# CPU2.net
KiCad netlist of a schematic drawn in Altium Designer
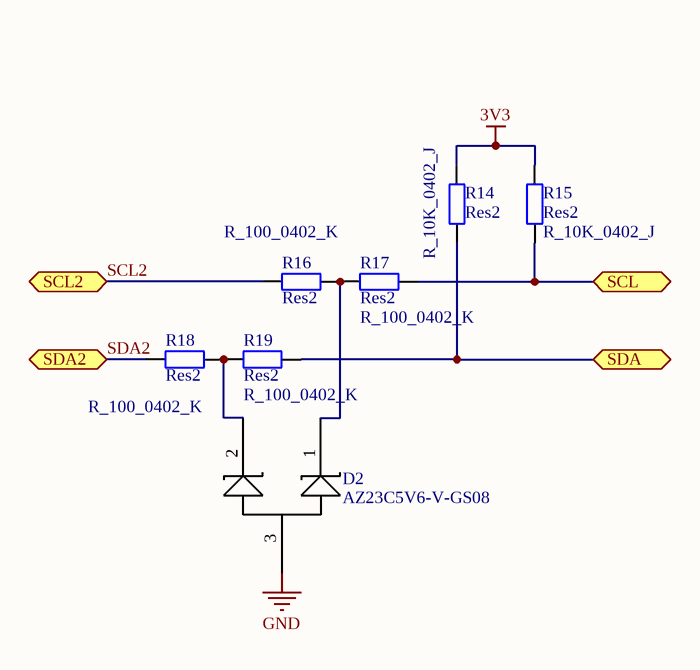
[diagram p0: CPU2.SchDoc]

(export (version "E")
  (design (tool "Eeschema 10.0.6"))
  (components
    (comp (ref "D2")
      (value "AZ23C5V6-V-GS08")
      (footprint "SOT-23_N")
      (description "Zener Diodes 5.6 Volt 0.3W 5% CA")
      (fields (field (name "MANUFACTURER") "Vishay Semiconductors"))
      (libsource (lib "BrewBit") (part "AZ23C5V6-V-GS08"))
    )
    (comp (ref "R14")
      (value "Res2")
      (footprint "R_0402")
      (description "Resistor")
      (fields (field (name "ALTIUM_VALUE") "R_10K_0402_J") (field (name "PUBLISHER") "Altium Limited"))
      (libsource (lib "") (part "Res2_1"))
    )
    (comp (ref "R15")
      (value "Res2")
      (footprint "R_0402")
      (description "Resistor")
      (fields (field (name "ALTIUM_VALUE") "R_10K_0402_J") (field (name "PUBLISHER") "Altium Limited"))
      (libsource (lib "") (part "Res2_1"))
    )
    (comp (ref "R16")
      (value "Res2")
      (footprint "R_0402")
      (description "Resistor")
      (fields (field (name "ALTIUM_VALUE") "R_100_0402_K") (field (name "PUBLISHER") "Altium Limited"))
      (libsource (lib "Miscellaneous Devices") (part "Res2"))
    )
    (comp (ref "R17")
      (value "Res2")
      (footprint "R_0402")
      (description "Resistor")
      (fields (field (name "ALTIUM_VALUE") "R_100_0402_K") (field (name "PUBLISHER") "Altium Limited"))
      (libsource (lib "Miscellaneous Devices") (part "Res2"))
    )
    (comp (ref "R18")
      (value "Res2")
      (footprint "R_0402")
      (description "Resistor")
      (fields (field (name "ALTIUM_VALUE") "R_100_0402_K") (field (name "PUBLISHER") "Altium Limited"))
      (libsource (lib "Miscellaneous Devices") (part "Res2"))
    )
    (comp (ref "R19")
      (value "Res2")
      (footprint "R_0402")
      (description "Resistor")
      (fields (field (name "ALTIUM_VALUE") "R_100_0402_K") (field (name "PUBLISHER") "Altium Limited"))
      (libsource (lib "Miscellaneous Devices") (part "Res2"))
    )
  )
  (nets
    (net (code "1") (name "/SCL") (class "Default")
      (node (ref "R15") (pin "1") (pinfunction "1_1") (pintype "passive"))
      (node (ref "R17") (pin "2") (pinfunction "2_2") (pintype "passive"))
    )
    (net (code "2") (name "/SCL2") (class "Default")
      (node (ref "R16") (pin "1") (pinfunction "1_1") (pintype "passive"))
    )
    (net (code "3") (name "/SDA") (class "Default")
      (node (ref "R14") (pin "1") (pinfunction "1_1") (pintype "passive"))
      (node (ref "R19") (pin "2") (pinfunction "2_2") (pintype "passive"))
    )
    (net (code "4") (name "/SDA2") (class "Default")
      (node (ref "R18") (pin "1") (pinfunction "1_1") (pintype "passive"))
    )
    (net (code "5") (name "3V3") (class "Default")
      (node (ref "R14") (pin "2") (pinfunction "2_2") (pintype "passive"))
      (node (ref "R15") (pin "2") (pinfunction "2_2") (pintype "passive"))
    )
    (net (code "6") (name "GND") (class "Default")
      (node (ref "D2") (pin "3") (pinfunction "3_3") (pintype "passive"))
    )
    (net (code "7") (name "Net-(D2-Pad1)") (class "Default")
      (node (ref "D2") (pin "1") (pinfunction "1_1") (pintype "passive"))
      (node (ref "R16") (pin "2") (pinfunction "2_2") (pintype "passive"))
      (node (ref "R17") (pin "1") (pinfunction "1_1") (pintype "passive"))
    )
    (net (code "8") (name "Net-(D2-Pad2)") (class "Default")
      (node (ref "D2") (pin "2") (pinfunction "2_2") (pintype "passive"))
      (node (ref "R18") (pin "2") (pinfunction "2_2") (pintype "passive"))
      (node (ref "R19") (pin "1") (pinfunction "1_1") (pintype "passive"))
    )
  )
)
